# untitled.net
KiCad netlist of a schematic drawn in EAGLE
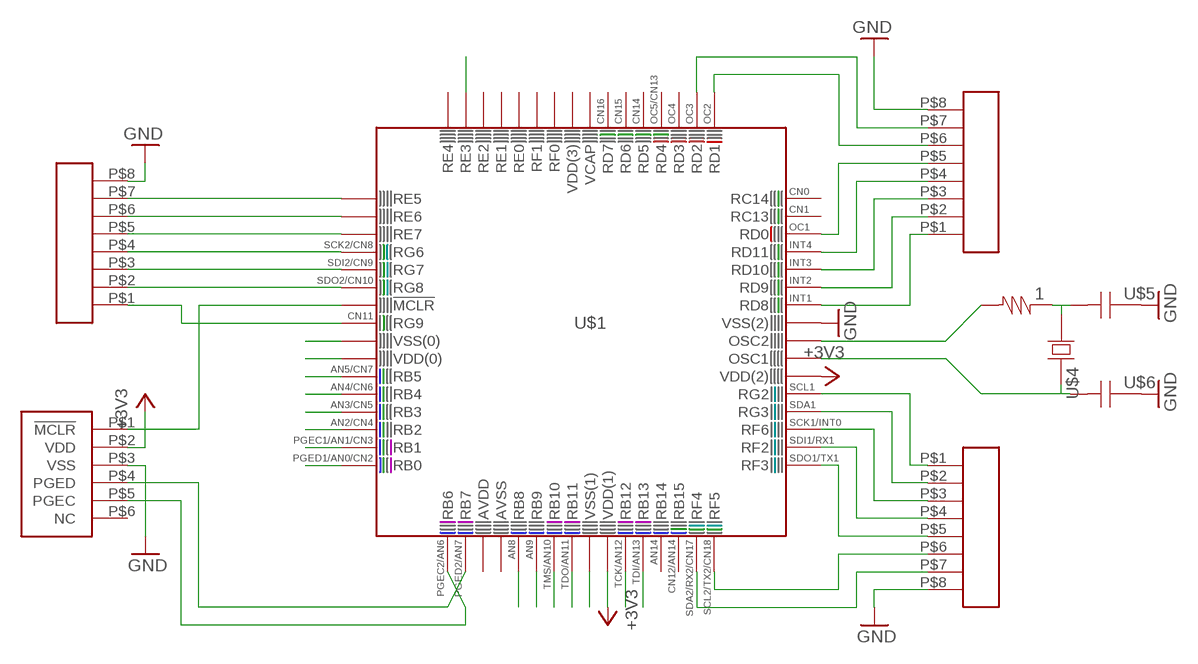
[diagram p0: schematic, sheet 1]

(export (version "E")
  (design (tool "Eeschema 10.0.6"))
  (components
    (comp (ref "1")
      (value ".RES-0603")
      (footprint "eagle-import:E_0603")
      (libsource (lib "eagle-import") (part ".RES-0603"))
    )
    (comp (ref "U$1")
      (value "PIC32MX5XX")
      (footprint "eagle-import:E_QFN64")
      (libsource (lib "eagle-import") (part "PIC32MX5XX"))
    )
    (comp (ref "U$2")
      (value "CON_8PIN")
      (footprint "eagle-import:CON_8PIN")
      (libsource (lib "eagle-import") (part "CON_8PIN"))
    )
    (comp (ref "U$3")
      (value "CON_8PIN")
      (footprint "eagle-import:CON_8PIN")
      (libsource (lib "eagle-import") (part "CON_8PIN"))
    )
    (comp (ref "U$4")
      (value ".XTAL-CTS406")
      (footprint "eagle-import:SMT_CRYSTAL")
      (libsource (lib "eagle-import") (part ".XTAL-CTS406"))
    )
    (comp (ref "U$5")
      (value ".CAP-0603")
      (footprint "eagle-import:E_0603")
      (libsource (lib "eagle-import") (part ".CAP-0603"))
    )
    (comp (ref "U$6")
      (value ".CAP-0603")
      (footprint "eagle-import:E_0603")
      (libsource (lib "eagle-import") (part ".CAP-0603"))
    )
    (comp (ref "U$27")
      (value "CON_8PIN")
      (footprint "eagle-import:CON_8PIN")
      (libsource (lib "eagle-import") (part "CON_8PIN"))
    )
    (comp (ref "U$29")
      (value "CON_ICSP-PIC")
      (footprint "eagle-import:CON_ICSP-PIC")
      (libsource (lib "eagle-import") (part "CON_ICSP-PIC"))
    )
  )
  (nets
    (net (code "1") (name "+3V3") (class "Default")
      (node (ref "U$1") (pin "P$26") (pinfunction "VDD(1)_P$26") (pintype "bidirectional"))
      (node (ref "U$1") (pin "P$38") (pinfunction "VDD(2)_P$38") (pintype "bidirectional"))
      (node (ref "U$29") (pin "P$2") (pinfunction "VDD_P$2") (pintype "bidirectional"))
    )
    (net (code "2") (name "GND") (class "Default")
      (node (ref "U$1") (pin "P$41") (pinfunction "VSS(2)_P$41") (pintype "bidirectional"))
      (node (ref "U$2") (pin "P$8") (pinfunction "P$8_P$8") (pintype "bidirectional"))
      (node (ref "U$27") (pin "P$8") (pinfunction "P$8_P$8") (pintype "bidirectional"))
      (node (ref "U$29") (pin "P$3") (pinfunction "VSS_P$3") (pintype "bidirectional"))
      (node (ref "U$3") (pin "P$8") (pinfunction "P$8_P$8") (pintype "bidirectional"))
      (node (ref "U$5") (pin "P$2") (pinfunction "P$2_P$2") (pintype "bidirectional"))
      (node (ref "U$6") (pin "P$2") (pinfunction "P$2_P$2") (pintype "bidirectional"))
    )
    (net (code "3") (name "Net-(1-PadP$2)") (class "Default")
      (node (ref "1") (pin "P$2") (pinfunction "P$2_P$2") (pintype "bidirectional"))
      (node (ref "U$4") (pin "P$1") (pinfunction "P$1_P$1") (pintype "bidirectional"))
      (node (ref "U$5") (pin "P$1") (pinfunction "P$1_P$1") (pintype "bidirectional"))
    )
    (net (code "4") (name "Net-(U$1-OSC1)") (class "Default")
      (node (ref "U$1") (pin "P$39") (pinfunction "OSC1_P$39") (pintype "bidirectional"))
      (node (ref "U$4") (pin "P$3") (pinfunction "P$2_P$3") (pintype "bidirectional"))
      (node (ref "U$6") (pin "P$1") (pinfunction "P$1_P$1") (pintype "bidirectional"))
    )
    (net (code "5") (name "Net-(U$1-OSC2)") (class "Default")
      (node (ref "1") (pin "P$1") (pinfunction "P$1_P$1") (pintype "bidirectional"))
      (node (ref "U$1") (pin "P$40") (pinfunction "OSC2_P$40") (pintype "bidirectional"))
    )
    (net (code "6") (name "Net-(U$1-RB6)") (class "Default")
      (node (ref "U$1") (pin "P$17") (pinfunction "RB6_P$17") (pintype "bidirectional"))
      (node (ref "U$29") (pin "P$5") (pinfunction "PGEC_P$5") (pintype "bidirectional"))
    )
    (net (code "7") (name "Net-(U$1-RB7)") (class "Default")
      (node (ref "U$1") (pin "P$18") (pinfunction "RB7_P$18") (pintype "bidirectional"))
      (node (ref "U$29") (pin "P$4") (pinfunction "PGED_P$4") (pintype "bidirectional"))
    )
    (net (code "8") (name "Net-(U$1-RD0)") (class "Default")
      (node (ref "U$1") (pin "P$46") (pinfunction "RD0_P$46") (pintype "bidirectional"))
      (node (ref "U$3") (pin "P$5") (pinfunction "P$5_P$5") (pintype "bidirectional"))
    )
    (net (code "9") (name "Net-(U$1-RD1)") (class "Default")
      (node (ref "U$1") (pin "P$49") (pinfunction "RD1_P$49") (pintype "bidirectional"))
      (node (ref "U$3") (pin "P$6") (pinfunction "P$6_P$6") (pintype "bidirectional"))
    )
    (net (code "10") (name "Net-(U$1-RD2)") (class "Default")
      (node (ref "U$1") (pin "P$50") (pinfunction "RD2_P$50") (pintype "bidirectional"))
      (node (ref "U$3") (pin "P$7") (pinfunction "P$7_P$7") (pintype "bidirectional"))
    )
    (net (code "11") (name "Net-(U$1-RD8)") (class "Default")
      (node (ref "U$1") (pin "P$42") (pinfunction "RD8_P$42") (pintype "bidirectional"))
      (node (ref "U$3") (pin "P$1") (pinfunction "P$1_P$1") (pintype "bidirectional"))
    )
    (net (code "12") (name "Net-(U$1-RD9)") (class "Default")
      (node (ref "U$1") (pin "P$43") (pinfunction "RD9_P$43") (pintype "bidirectional"))
      (node (ref "U$3") (pin "P$2") (pinfunction "P$2_P$2") (pintype "bidirectional"))
    )
    (net (code "13") (name "Net-(U$1-RD10)") (class "Default")
      (node (ref "U$1") (pin "P$44") (pinfunction "RD10_P$44") (pintype "bidirectional"))
      (node (ref "U$3") (pin "P$3") (pinfunction "P$3_P$3") (pintype "bidirectional"))
    )
    (net (code "14") (name "Net-(U$1-RD11)") (class "Default")
      (node (ref "U$1") (pin "P$45") (pinfunction "RD11_P$45") (pintype "bidirectional"))
      (node (ref "U$3") (pin "P$4") (pinfunction "P$4_P$4") (pintype "bidirectional"))
    )
    (net (code "15") (name "Net-(U$1-RE5)") (class "Default")
      (node (ref "U$1") (pin "P$1") (pinfunction "RE5_P$1") (pintype "bidirectional"))
      (node (ref "U$2") (pin "P$7") (pinfunction "P$7_P$7") (pintype "bidirectional"))
    )
    (net (code "16") (name "Net-(U$1-RE6)") (class "Default")
      (node (ref "U$1") (pin "P$2") (pinfunction "RE6_P$2") (pintype "bidirectional"))
      (node (ref "U$2") (pin "P$6") (pinfunction "P$6_P$6") (pintype "bidirectional"))
    )
    (net (code "17") (name "Net-(U$1-RE7)") (class "Default")
      (node (ref "U$1") (pin "P$3") (pinfunction "RE7_P$3") (pintype "bidirectional"))
      (node (ref "U$2") (pin "P$5") (pinfunction "P$5_P$5") (pintype "bidirectional"))
    )
    (net (code "18") (name "Net-(U$1-RF2)") (class "Default")
      (node (ref "U$1") (pin "P$34") (pinfunction "RF2_P$34") (pintype "bidirectional"))
      (node (ref "U$27") (pin "P$4") (pinfunction "P$4_P$4") (pintype "bidirectional"))
    )
    (net (code "19") (name "Net-(U$1-RF3)") (class "Default")
      (node (ref "U$1") (pin "P$33") (pinfunction "RF3_P$33") (pintype "bidirectional"))
      (node (ref "U$27") (pin "P$5") (pinfunction "P$5_P$5") (pintype "bidirectional"))
    )
    (net (code "20") (name "Net-(U$1-RF4)") (class "Default")
      (node (ref "U$1") (pin "P$31") (pinfunction "RF4_P$31") (pintype "bidirectional"))
      (node (ref "U$27") (pin "P$7") (pinfunction "P$7_P$7") (pintype "bidirectional"))
    )
    (net (code "21") (name "Net-(U$1-RF5)") (class "Default")
      (node (ref "U$1") (pin "P$32") (pinfunction "RF5_P$32") (pintype "bidirectional"))
      (node (ref "U$27") (pin "P$6") (pinfunction "P$6_P$6") (pintype "bidirectional"))
    )
    (net (code "22") (name "Net-(U$1-RF6)") (class "Default")
      (node (ref "U$1") (pin "P$35") (pinfunction "RF6_P$35") (pintype "bidirectional"))
      (node (ref "U$27") (pin "P$3") (pinfunction "P$3_P$3") (pintype "bidirectional"))
    )
    (net (code "23") (name "Net-(U$1-RG2)") (class "Default")
      (node (ref "U$1") (pin "P$37") (pinfunction "RG2_P$37") (pintype "bidirectional"))
      (node (ref "U$27") (pin "P$1") (pinfunction "P$1_P$1") (pintype "bidirectional"))
    )
    (net (code "24") (name "Net-(U$1-RG3)") (class "Default")
      (node (ref "U$1") (pin "P$36") (pinfunction "RG3_P$36") (pintype "bidirectional"))
      (node (ref "U$27") (pin "P$2") (pinfunction "P$2_P$2") (pintype "bidirectional"))
    )
    (net (code "25") (name "Net-(U$1-RG6)") (class "Default")
      (node (ref "U$1") (pin "P$4") (pinfunction "RG6_P$4") (pintype "bidirectional"))
      (node (ref "U$2") (pin "P$4") (pinfunction "P$4_P$4") (pintype "bidirectional"))
    )
    (net (code "26") (name "Net-(U$1-RG7)") (class "Default")
      (node (ref "U$1") (pin "P$5") (pinfunction "RG7_P$5") (pintype "bidirectional"))
      (node (ref "U$2") (pin "P$3") (pinfunction "P$3_P$3") (pintype "bidirectional"))
    )
    (net (code "27") (name "Net-(U$1-RG8)") (class "Default")
      (node (ref "U$1") (pin "P$6") (pinfunction "RG8_P$6") (pintype "bidirectional"))
      (node (ref "U$2") (pin "P$2") (pinfunction "P$2_P$2") (pintype "bidirectional"))
    )
    (net (code "28") (name "Net-(U$1-RG9)") (class "Default")
      (node (ref "U$1") (pin "P$8") (pinfunction "RG9_P$8") (pintype "bidirectional"))
      (node (ref "U$2") (pin "P$1") (pinfunction "P$1_P$1") (pintype "bidirectional"))
    )
    (net (code "29") (name "Net-(U$1-~{MCLR})") (class "Default")
      (node (ref "U$1") (pin "P$7") (pinfunction "~{MCLR}_P$7") (pintype "bidirectional"))
      (node (ref "U$29") (pin "P$1") (pinfunction "~{MCLR}_P$1") (pintype "bidirectional"))
    )
    (net (code "30") (name "unconnected-(U$1-AVDD-PadP$19)") (class "Default")
      (node (ref "U$1") (pin "P$19") (pinfunction "AVDD_P$19") (pintype "bidirectional"))
    )
    (net (code "31") (name "unconnected-(U$1-AVSS-PadP$20)") (class "Default")
      (node (ref "U$1") (pin "P$20") (pinfunction "AVSS_P$20") (pintype "bidirectional"))
    )
    (net (code "32") (name "unconnected-(U$1-RB0-PadP$16)") (class "Default")
      (node (ref "U$1") (pin "P$16") (pinfunction "RB0_P$16") (pintype "bidirectional"))
    )
    (net (code "33") (name "unconnected-(U$1-RB1-PadP$15)") (class "Default")
      (node (ref "U$1") (pin "P$15") (pinfunction "RB1_P$15") (pintype "bidirectional"))
    )
    (net (code "34") (name "unconnected-(U$1-RB2-PadP$14)") (class "Default")
      (node (ref "U$1") (pin "P$14") (pinfunction "RB2_P$14") (pintype "bidirectional"))
    )
    (net (code "35") (name "unconnected-(U$1-RB3-PadP$13)") (class "Default")
      (node (ref "U$1") (pin "P$13") (pinfunction "RB3_P$13") (pintype "bidirectional"))
    )
    (net (code "36") (name "unconnected-(U$1-RB4-PadP$12)") (class "Default")
      (node (ref "U$1") (pin "P$12") (pinfunction "RB4_P$12") (pintype "bidirectional"))
    )
    (net (code "37") (name "unconnected-(U$1-RB5-PadP$11)") (class "Default")
      (node (ref "U$1") (pin "P$11") (pinfunction "RB5_P$11") (pintype "bidirectional"))
    )
    (net (code "38") (name "unconnected-(U$1-RB8-PadP$21)") (class "Default")
      (node (ref "U$1") (pin "P$21") (pinfunction "RB8_P$21") (pintype "bidirectional"))
    )
    (net (code "39") (name "unconnected-(U$1-RB9-PadP$22)") (class "Default")
      (node (ref "U$1") (pin "P$22") (pinfunction "RB9_P$22") (pintype "bidirectional"))
    )
    (net (code "40") (name "unconnected-(U$1-RB10-PadP$23)") (class "Default")
      (node (ref "U$1") (pin "P$23") (pinfunction "RB10_P$23") (pintype "bidirectional"))
    )
    (net (code "41") (name "unconnected-(U$1-RB11-PadP$24)") (class "Default")
      (node (ref "U$1") (pin "P$24") (pinfunction "RB11_P$24") (pintype "bidirectional"))
    )
    (net (code "42") (name "unconnected-(U$1-RB12-PadP$27)") (class "Default")
      (node (ref "U$1") (pin "P$27") (pinfunction "RB12_P$27") (pintype "bidirectional"))
    )
    (net (code "43") (name "unconnected-(U$1-RB13-PadP$28)") (class "Default")
      (node (ref "U$1") (pin "P$28") (pinfunction "RB13_P$28") (pintype "bidirectional"))
    )
    (net (code "44") (name "unconnected-(U$1-RB14-PadP$29)") (class "Default")
      (node (ref "U$1") (pin "P$29") (pinfunction "RB14_P$29") (pintype "bidirectional"))
    )
    (net (code "45") (name "unconnected-(U$1-RB15-PadP$30)") (class "Default")
      (node (ref "U$1") (pin "P$30") (pinfunction "RB15_P$30") (pintype "bidirectional"))
    )
    (net (code "46") (name "unconnected-(U$1-RC13-PadP$47)") (class "Default")
      (node (ref "U$1") (pin "P$47") (pinfunction "RC13_P$47") (pintype "bidirectional"))
    )
    (net (code "47") (name "unconnected-(U$1-RC14-PadP$48)") (class "Default")
      (node (ref "U$1") (pin "P$48") (pinfunction "RC14_P$48") (pintype "bidirectional"))
    )
    (net (code "48") (name "unconnected-(U$1-RD3-PadP$51)") (class "Default")
      (node (ref "U$1") (pin "P$51") (pinfunction "RD3_P$51") (pintype "bidirectional"))
    )
    (net (code "49") (name "unconnected-(U$1-RD4-PadP$52)") (class "Default")
      (node (ref "U$1") (pin "P$52") (pinfunction "RD4_P$52") (pintype "bidirectional"))
    )
    (net (code "50") (name "unconnected-(U$1-RD5-PadP$53)") (class "Default")
      (node (ref "U$1") (pin "P$53") (pinfunction "RD5_P$53") (pintype "bidirectional"))
    )
    (net (code "51") (name "unconnected-(U$1-RD6-PadP$54)") (class "Default")
      (node (ref "U$1") (pin "P$54") (pinfunction "RD6_P$54") (pintype "bidirectional"))
    )
    (net (code "52") (name "unconnected-(U$1-RD7-PadP$55)") (class "Default")
      (node (ref "U$1") (pin "P$55") (pinfunction "RD7_P$55") (pintype "bidirectional"))
    )
    (net (code "53") (name "unconnected-(U$1-RE0-PadP$60)") (class "Default")
      (node (ref "U$1") (pin "P$60") (pinfunction "RE0_P$60") (pintype "bidirectional"))
    )
    (net (code "54") (name "unconnected-(U$1-RE1-PadP$61)") (class "Default")
      (node (ref "U$1") (pin "P$61") (pinfunction "RE1_P$61") (pintype "bidirectional"))
    )
    (net (code "55") (name "unconnected-(U$1-RE2-PadP$62)") (class "Default")
      (node (ref "U$1") (pin "P$62") (pinfunction "RE2_P$62") (pintype "bidirectional"))
    )
    (net (code "56") (name "unconnected-(U$1-RE3-PadP$63)") (class "Default")
      (node (ref "U$1") (pin "P$63") (pinfunction "RE3_P$63") (pintype "bidirectional"))
    )
    (net (code "57") (name "unconnected-(U$1-RE4-PadP$64)") (class "Default")
      (node (ref "U$1") (pin "P$64") (pinfunction "RE4_P$64") (pintype "bidirectional"))
    )
    (net (code "58") (name "unconnected-(U$1-RF0-PadP$58)") (class "Default")
      (node (ref "U$1") (pin "P$58") (pinfunction "RF0_P$58") (pintype "bidirectional"))
    )
    (net (code "59") (name "unconnected-(U$1-RF1-PadP$59)") (class "Default")
      (node (ref "U$1") (pin "P$59") (pinfunction "RF1_P$59") (pintype "bidirectional"))
    )
    (net (code "60") (name "unconnected-(U$1-VCAP-PadP$56)") (class "Default")
      (node (ref "U$1") (pin "P$56") (pinfunction "VCAP_P$56") (pintype "bidirectional"))
    )
    (net (code "61") (name "unconnected-(U$1-VDD(0)-PadP$10)") (class "Default")
      (node (ref "U$1") (pin "P$10") (pinfunction "VDD(0)_P$10") (pintype "bidirectional"))
    )
    (net (code "62") (name "unconnected-(U$1-VDD(3)-PadP$57)") (class "Default")
      (node (ref "U$1") (pin "P$57") (pinfunction "VDD(3)_P$57") (pintype "bidirectional"))
    )
    (net (code "63") (name "unconnected-(U$1-VSS(0)-PadP$9)") (class "Default")
      (node (ref "U$1") (pin "P$9") (pinfunction "VSS(0)_P$9") (pintype "bidirectional"))
    )
    (net (code "64") (name "unconnected-(U$1-VSS(1)-PadP$25)") (class "Default")
      (node (ref "U$1") (pin "P$25") (pinfunction "VSS(1)_P$25") (pintype "bidirectional"))
    )
    (net (code "65") (name "unconnected-(U$29-NC-PadP$6)") (class "Default")
      (node (ref "U$29") (pin "P$6") (pinfunction "NC_P$6") (pintype "bidirectional"))
    )
  )
)
